# bmsSlave_main.net
KiCad netlist of a schematic drawn in Altium Designer
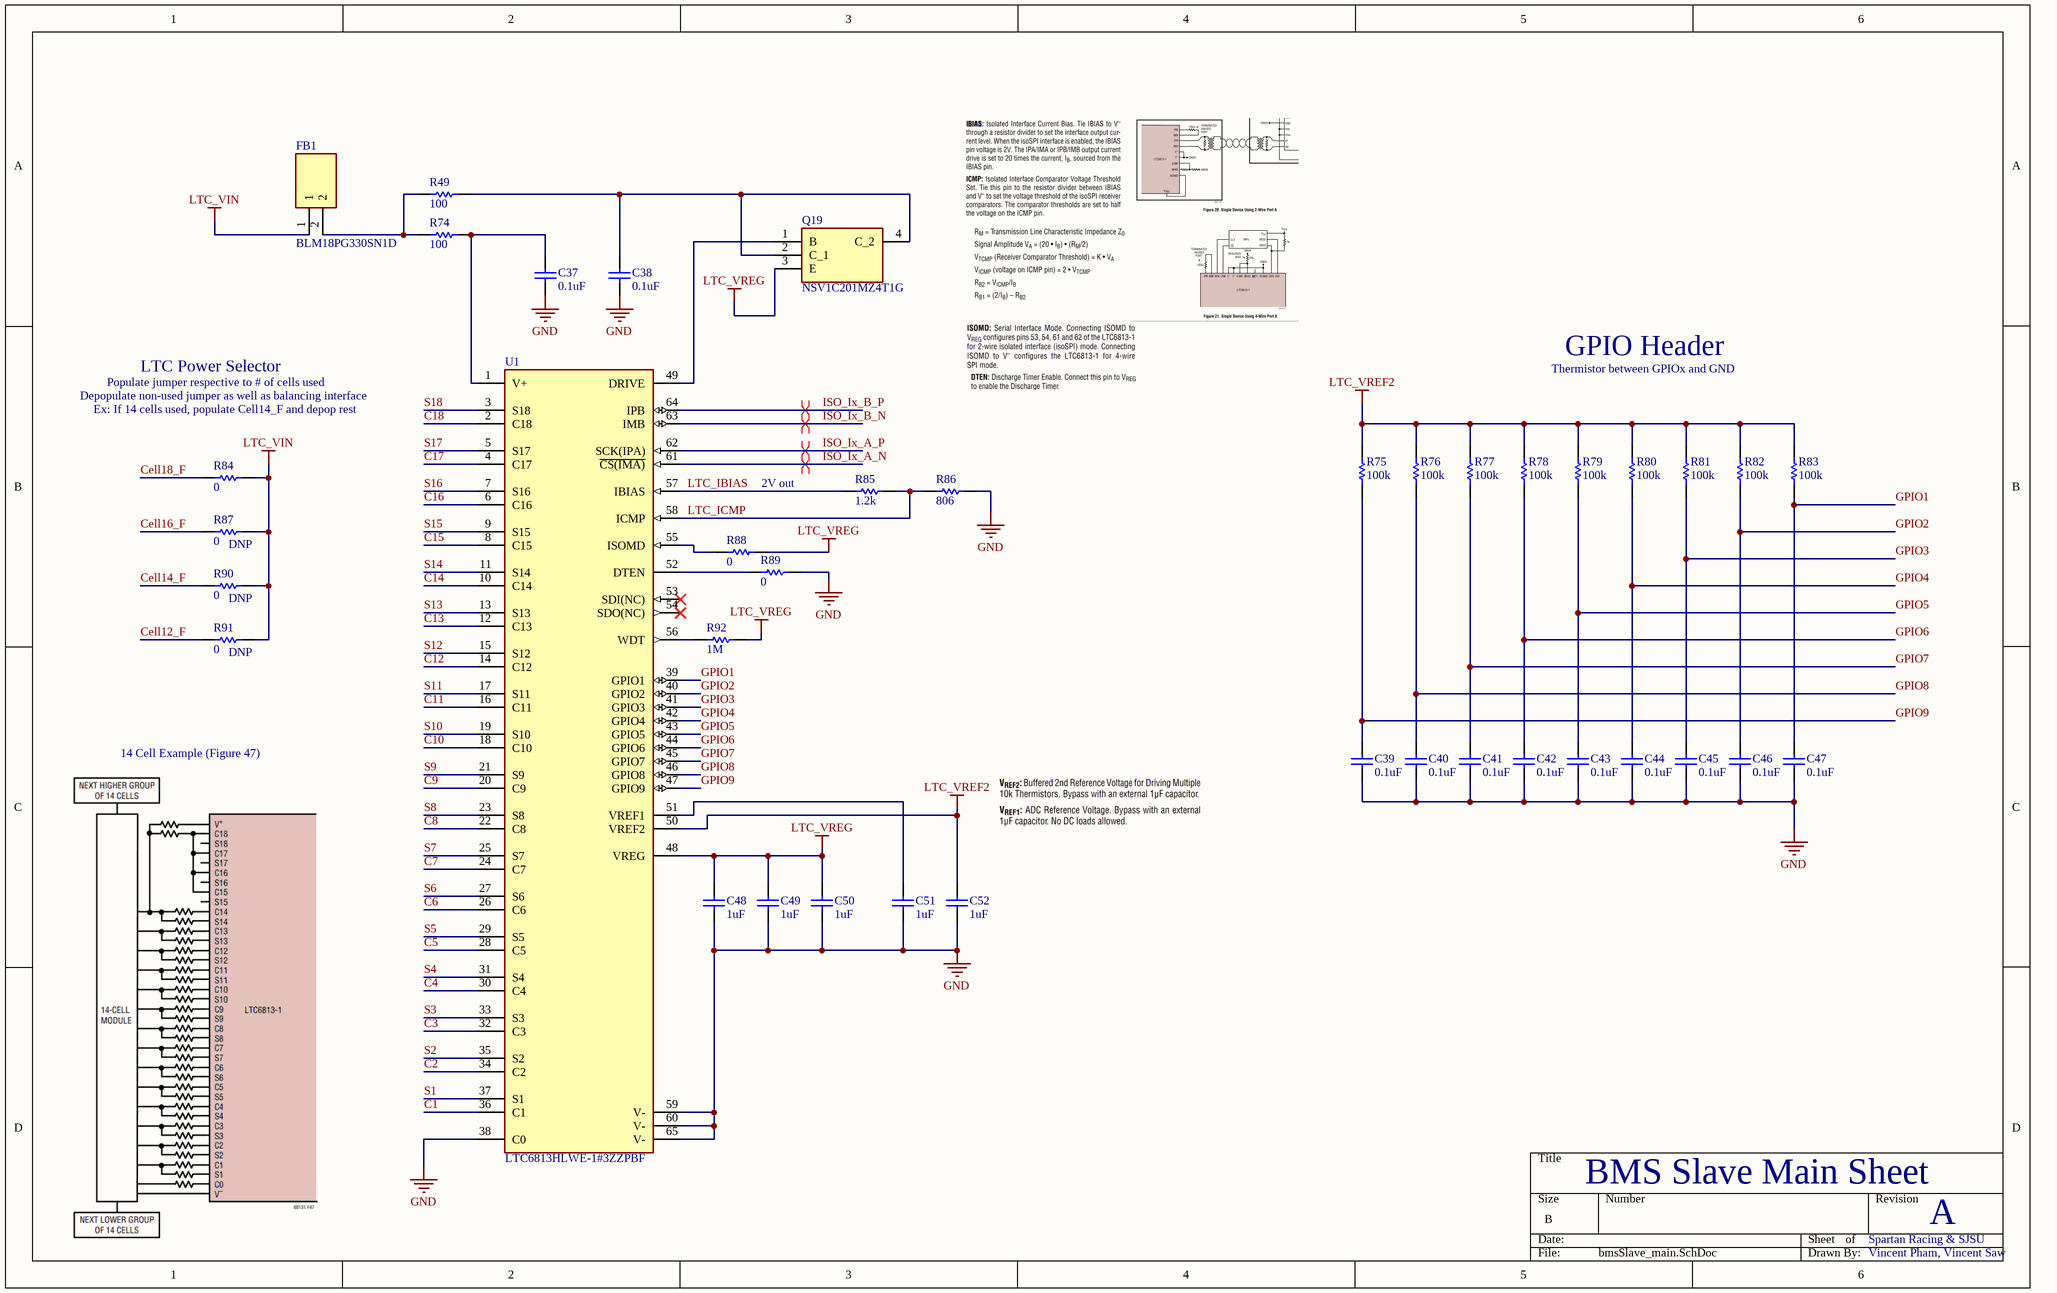
[diagram p0: bmsSlave_main.SchDoc]

(export (version "E")
  (design (tool "Eeschema 10.0.6"))
  (components
    (comp (ref "C37")
      (value "0.1uF")
      (footprint "C0603")
      (description "Capacitor")
      (libsource (lib "Simulation Generic Components") (part "Capacitor"))
    )
    (comp (ref "C38")
      (value "0.1uF")
      (footprint "C0603")
      (description "Capacitor")
      (libsource (lib "Simulation Generic Components") (part "Capacitor"))
    )
    (comp (ref "C39")
      (value "0.1uF")
      (footprint "C0603")
      (description "Capacitor")
      (libsource (lib "Simulation Generic Components") (part "Capacitor"))
    )
    (comp (ref "C40")
      (value "0.1uF")
      (footprint "C0603")
      (description "Capacitor")
      (libsource (lib "Simulation Generic Components") (part "Capacitor"))
    )
    (comp (ref "C41")
      (value "0.1uF")
      (footprint "C0603")
      (description "Capacitor")
      (libsource (lib "Simulation Generic Components") (part "Capacitor"))
    )
    (comp (ref "C42")
      (value "0.1uF")
      (footprint "C0603")
      (description "Capacitor")
      (libsource (lib "Simulation Generic Components") (part "Capacitor"))
    )
    (comp (ref "C43")
      (value "0.1uF")
      (footprint "C0603")
      (description "Capacitor")
      (libsource (lib "Simulation Generic Components") (part "Capacitor"))
    )
    (comp (ref "C44")
      (value "0.1uF")
      (footprint "C0603")
      (description "Capacitor")
      (libsource (lib "Simulation Generic Components") (part "Capacitor"))
    )
    (comp (ref "C45")
      (value "0.1uF")
      (footprint "C0603")
      (description "Capacitor")
      (libsource (lib "Simulation Generic Components") (part "Capacitor"))
    )
    (comp (ref "C46")
      (value "0.1uF")
      (footprint "C0603")
      (description "Capacitor")
      (libsource (lib "Simulation Generic Components") (part "Capacitor"))
    )
    (comp (ref "C47")
      (value "0.1uF")
      (footprint "C0603")
      (description "Capacitor")
      (libsource (lib "Simulation Generic Components") (part "Capacitor"))
    )
    (comp (ref "C48")
      (value "1uF")
      (footprint "C0603")
      (description "Capacitor")
      (libsource (lib "Simulation Generic Components") (part "Capacitor"))
    )
    (comp (ref "C49")
      (value "1uF")
      (footprint "C0603")
      (description "Capacitor")
      (libsource (lib "Simulation Generic Components") (part "Capacitor"))
    )
    (comp (ref "C50")
      (value "1uF")
      (footprint "C0603")
      (description "Capacitor")
      (libsource (lib "Simulation Generic Components") (part "Capacitor"))
    )
    (comp (ref "C51")
      (value "1uF")
      (footprint "C0603")
      (description "Capacitor")
      (libsource (lib "Simulation Generic Components") (part "Capacitor"))
    )
    (comp (ref "C52")
      (value "1uF")
      (footprint "C0603")
      (description "Capacitor")
      (libsource (lib "Simulation Generic Components") (part "Capacitor"))
    )
    (comp (ref "FB1")
      (value "BLM18PG330SN1D")
      (footprint "BEADC1608X95N")
      (description "Ferrite Bead")
      (fields (field (name "MOUSER PART NUMBER") "81-BLM18PG330SN1D"))
      (libsource (lib "bmsSlave") (part "BLM18PG330SN1D"))
    )
    (comp (ref "Q19")
      (value "NSV1C201MZ4T1G")
      (footprint "SOT230P700X175-4N:SOT230P700X175-4N")
      (description "Transistor")
      (fields (field (name "MOUSER PART NUMBER") "863-NSV1C201MZ4T1G"))
      (libsource (lib "*") (part "NSV1C201MZ4T1G"))
    )
    (comp (ref "R49")
      (value "100")
      (footprint "R0603")
      (description "Resistor")
      (libsource (lib "Simulation Generic Components") (part "Resistor"))
    )
    (comp (ref "R74")
      (value "100")
      (footprint "R0603")
      (description "Resistor")
      (libsource (lib "Simulation Generic Components") (part "Resistor"))
    )
    (comp (ref "R75")
      (value "100k")
      (footprint "R0603")
      (description "Resistor")
      (libsource (lib "Simulation Generic Components") (part "Resistor"))
    )
    (comp (ref "R76")
      (value "100k")
      (footprint "R0603")
      (description "Resistor")
      (libsource (lib "Simulation Generic Components") (part "Resistor"))
    )
    (comp (ref "R77")
      (value "100k")
      (footprint "R0603")
      (description "Resistor")
      (libsource (lib "Simulation Generic Components") (part "Resistor"))
    )
    (comp (ref "R78")
      (value "100k")
      (footprint "R0603")
      (description "Resistor")
      (libsource (lib "Simulation Generic Components") (part "Resistor"))
    )
    (comp (ref "R79")
      (value "100k")
      (footprint "R0603")
      (description "Resistor")
      (libsource (lib "Simulation Generic Components") (part "Resistor"))
    )
    (comp (ref "R80")
      (value "100k")
      (footprint "R0603")
      (description "Resistor")
      (libsource (lib "Simulation Generic Components") (part "Resistor"))
    )
    (comp (ref "R81")
      (value "100k")
      (footprint "R0603")
      (description "Resistor")
      (libsource (lib "Simulation Generic Components") (part "Resistor"))
    )
    (comp (ref "R82")
      (value "100k")
      (footprint "R0603")
      (description "Resistor")
      (libsource (lib "Simulation Generic Components") (part "Resistor"))
    )
    (comp (ref "R83")
      (value "100k")
      (footprint "R0603")
      (description "Resistor")
      (libsource (lib "Simulation Generic Components") (part "Resistor"))
    )
    (comp (ref "R84")
      (value "0")
      (footprint "R0603")
      (description "Resistor")
      (libsource (lib "Simulation Generic Components") (part "Resistor"))
    )
    (comp (ref "R85")
      (value "1.2k")
      (footprint "R0603")
      (description "Resistor")
      (libsource (lib "Simulation Generic Components") (part "Resistor"))
    )
    (comp (ref "R86")
      (value "806")
      (footprint "R0603")
      (description "Resistor")
      (libsource (lib "Simulation Generic Components") (part "Resistor"))
    )
    (comp (ref "R87")
      (value "0")
      (footprint "R0603")
      (description "Resistor")
      (libsource (lib "Simulation Generic Components") (part "Resistor"))
    )
    (comp (ref "R88")
      (value "0")
      (footprint "R0603")
      (description "Resistor")
      (libsource (lib "Simulation Generic Components") (part "Resistor"))
    )
    (comp (ref "R89")
      (value "0")
      (footprint "R0603")
      (description "Resistor")
      (libsource (lib "Simulation Generic Components") (part "Resistor"))
    )
    (comp (ref "R90")
      (value "0")
      (footprint "R0603")
      (description "Resistor")
      (libsource (lib "Simulation Generic Components") (part "Resistor"))
    )
    (comp (ref "R91")
      (value "0")
      (footprint "R0603")
      (description "Resistor")
      (libsource (lib "Simulation Generic Components") (part "Resistor"))
    )
    (comp (ref "R92")
      (value "1M")
      (footprint "R0603")
      (description "Resistor")
      (libsource (lib "Simulation Generic Components") (part "Resistor"))
    )
    (comp (ref "U1")
      (value "LTC6813HLWE-1#3ZZPBF")
      (footprint "FP-LWE-64-05-08-1982-MFG")
      (description "18 CHANNEL MULTICELL BATTERY STA")
      (fields
        (field (name "OCTOPART") "https://octopart.com/ltc6813hlwe-1%233zzpbf-analog+devices-90390400")
        (field (name "MANUFACTURER") "Analog Devices")
      )
      (libsource (lib "Altium Content Vault") (part "0b74ddd223dcb5fcd0195e222fef2b3"))
    )
  )
  (nets
    (net (code "1") (name "/C1") (class "Default")
      (node (ref "U1") (pin "36") (pinfunction "C1_36") (pintype "passive"))
    )
    (net (code "2") (name "/C2") (class "Default")
      (node (ref "U1") (pin "34") (pinfunction "C2_34") (pintype "passive"))
    )
    (net (code "3") (name "/C3") (class "Default")
      (node (ref "U1") (pin "32") (pinfunction "C3_32") (pintype "passive"))
    )
    (net (code "4") (name "/C4") (class "Default")
      (node (ref "U1") (pin "30") (pinfunction "C4_30") (pintype "passive"))
    )
    (net (code "5") (name "/C5") (class "Default")
      (node (ref "U1") (pin "28") (pinfunction "C5_28") (pintype "passive"))
    )
    (net (code "6") (name "/C6") (class "Default")
      (node (ref "U1") (pin "26") (pinfunction "C6_26") (pintype "passive"))
    )
    (net (code "7") (name "/C7") (class "Default")
      (node (ref "U1") (pin "24") (pinfunction "C7_24") (pintype "passive"))
    )
    (net (code "8") (name "/C8") (class "Default")
      (node (ref "U1") (pin "22") (pinfunction "C8_22") (pintype "passive"))
    )
    (net (code "9") (name "/C9") (class "Default")
      (node (ref "U1") (pin "20") (pinfunction "C9_20") (pintype "passive"))
    )
    (net (code "10") (name "/C10") (class "Default")
      (node (ref "U1") (pin "18") (pinfunction "C10_18") (pintype "passive"))
    )
    (net (code "11") (name "/C11") (class "Default")
      (node (ref "U1") (pin "16") (pinfunction "C11_16") (pintype "passive"))
    )
    (net (code "12") (name "/C12") (class "Default")
      (node (ref "U1") (pin "14") (pinfunction "C12_14") (pintype "passive"))
    )
    (net (code "13") (name "/C13") (class "Default")
      (node (ref "U1") (pin "12") (pinfunction "C13_12") (pintype "passive"))
    )
    (net (code "14") (name "/C14") (class "Default")
      (node (ref "U1") (pin "10") (pinfunction "C14_10") (pintype "passive"))
    )
    (net (code "15") (name "/C15") (class "Default")
      (node (ref "U1") (pin "8") (pinfunction "C15_8") (pintype "passive"))
    )
    (net (code "16") (name "/C16") (class "Default")
      (node (ref "U1") (pin "6") (pinfunction "C16_6") (pintype "passive"))
    )
    (net (code "17") (name "/C17") (class "Default")
      (node (ref "U1") (pin "4") (pinfunction "C17_4") (pintype "passive"))
    )
    (net (code "18") (name "/C18") (class "Default")
      (node (ref "U1") (pin "2") (pinfunction "C18_2") (pintype "passive"))
    )
    (net (code "19") (name "/Cell12_F") (class "Default")
      (node (ref "R91") (pin "1") (pinfunction "1_1") (pintype "passive"))
    )
    (net (code "20") (name "/Cell14_F") (class "Default")
      (node (ref "R90") (pin "1") (pinfunction "1_1") (pintype "passive"))
    )
    (net (code "21") (name "/Cell16_F") (class "Default")
      (node (ref "R87") (pin "1") (pinfunction "1_1") (pintype "passive"))
    )
    (net (code "22") (name "/Cell18_F") (class "Default")
      (node (ref "R84") (pin "1") (pinfunction "1_1") (pintype "passive"))
    )
    (net (code "23") (name "/GPIO1") (class "Default")
      (node (ref "C47") (pin "1") (pinfunction "1_1") (pintype "passive"))
      (node (ref "R83") (pin "1") (pinfunction "1_1") (pintype "passive"))
      (node (ref "U1") (pin "39") (pinfunction "GPIO1_39") (pintype "bidirectional"))
    )
    (net (code "24") (name "/GPIO2") (class "Default")
      (node (ref "C46") (pin "1") (pinfunction "1_1") (pintype "passive"))
      (node (ref "R82") (pin "1") (pinfunction "1_1") (pintype "passive"))
      (node (ref "U1") (pin "40") (pinfunction "GPIO2_40") (pintype "bidirectional"))
    )
    (net (code "25") (name "/GPIO3") (class "Default")
      (node (ref "C45") (pin "1") (pinfunction "1_1") (pintype "passive"))
      (node (ref "R81") (pin "1") (pinfunction "1_1") (pintype "passive"))
      (node (ref "U1") (pin "41") (pinfunction "GPIO3_41") (pintype "bidirectional"))
    )
    (net (code "26") (name "/GPIO4") (class "Default")
      (node (ref "C44") (pin "1") (pinfunction "1_1") (pintype "passive"))
      (node (ref "R80") (pin "1") (pinfunction "1_1") (pintype "passive"))
      (node (ref "U1") (pin "42") (pinfunction "GPIO4_42") (pintype "bidirectional"))
    )
    (net (code "27") (name "/GPIO5") (class "Default")
      (node (ref "C43") (pin "1") (pinfunction "1_1") (pintype "passive"))
      (node (ref "R79") (pin "1") (pinfunction "1_1") (pintype "passive"))
      (node (ref "U1") (pin "43") (pinfunction "GPIO5_43") (pintype "bidirectional"))
    )
    (net (code "28") (name "/GPIO6") (class "Default")
      (node (ref "C42") (pin "1") (pinfunction "1_1") (pintype "passive"))
      (node (ref "R78") (pin "1") (pinfunction "1_1") (pintype "passive"))
      (node (ref "U1") (pin "44") (pinfunction "GPIO6_44") (pintype "bidirectional"))
    )
    (net (code "29") (name "/GPIO7") (class "Default")
      (node (ref "C41") (pin "1") (pinfunction "1_1") (pintype "passive"))
      (node (ref "R77") (pin "1") (pinfunction "1_1") (pintype "passive"))
      (node (ref "U1") (pin "45") (pinfunction "GPIO7_45") (pintype "bidirectional"))
    )
    (net (code "30") (name "/GPIO8") (class "Default")
      (node (ref "C40") (pin "1") (pinfunction "1_1") (pintype "passive"))
      (node (ref "R76") (pin "1") (pinfunction "1_1") (pintype "passive"))
      (node (ref "U1") (pin "46") (pinfunction "GPIO8_46") (pintype "bidirectional"))
    )
    (net (code "31") (name "/GPIO9") (class "Default")
      (node (ref "C39") (pin "1") (pinfunction "1_1") (pintype "passive"))
      (node (ref "R75") (pin "1") (pinfunction "1_1") (pintype "passive"))
      (node (ref "U1") (pin "47") (pinfunction "GPIO9_47") (pintype "bidirectional"))
    )
    (net (code "32") (name "/ISO_Ix_A_N") (class "Default")
      (node (ref "U1") (pin "61") (pinfunction "~{CS(IMA)}_61") (pintype "input"))
    )
    (net (code "33") (name "/ISO_Ix_A_P") (class "Default")
      (node (ref "U1") (pin "62") (pinfunction "SCK(IPA)_62") (pintype "input"))
    )
    (net (code "34") (name "/ISO_Ix_B_N") (class "Default")
      (node (ref "U1") (pin "63") (pinfunction "IMB_63") (pintype "bidirectional"))
    )
    (net (code "35") (name "/ISO_Ix_B_P") (class "Default")
      (node (ref "U1") (pin "64") (pinfunction "IPB_64") (pintype "bidirectional"))
    )
    (net (code "36") (name "/LTC_IBIAS") (class "Default")
      (node (ref "R85") (pin "2") (pinfunction "2_2") (pintype "passive"))
      (node (ref "U1") (pin "57") (pinfunction "IBIAS_57") (pintype "input"))
    )
    (net (code "37") (name "/LTC_ICMP") (class "Default")
      (node (ref "R85") (pin "1") (pinfunction "1_1") (pintype "passive"))
      (node (ref "R86") (pin "1") (pinfunction "1_1") (pintype "passive"))
      (node (ref "U1") (pin "58") (pinfunction "ICMP_58") (pintype "input"))
    )
    (net (code "38") (name "/S1") (class "Default")
      (node (ref "U1") (pin "37") (pinfunction "S1_37") (pintype "passive"))
    )
    (net (code "39") (name "/S2") (class "Default")
      (node (ref "U1") (pin "35") (pinfunction "S2_35") (pintype "passive"))
    )
    (net (code "40") (name "/S3") (class "Default")
      (node (ref "U1") (pin "33") (pinfunction "S3_33") (pintype "passive"))
    )
    (net (code "41") (name "/S4") (class "Default")
      (node (ref "U1") (pin "31") (pinfunction "S4_31") (pintype "passive"))
    )
    (net (code "42") (name "/S5") (class "Default")
      (node (ref "U1") (pin "29") (pinfunction "S5_29") (pintype "passive"))
    )
    (net (code "43") (name "/S6") (class "Default")
      (node (ref "U1") (pin "27") (pinfunction "S6_27") (pintype "passive"))
    )
    (net (code "44") (name "/S7") (class "Default")
      (node (ref "U1") (pin "25") (pinfunction "S7_25") (pintype "passive"))
    )
    (net (code "45") (name "/S8") (class "Default")
      (node (ref "U1") (pin "23") (pinfunction "S8_23") (pintype "passive"))
    )
    (net (code "46") (name "/S9") (class "Default")
      (node (ref "U1") (pin "21") (pinfunction "S9_21") (pintype "passive"))
    )
    (net (code "47") (name "/S10") (class "Default")
      (node (ref "U1") (pin "19") (pinfunction "S10_19") (pintype "passive"))
    )
    (net (code "48") (name "/S11") (class "Default")
      (node (ref "U1") (pin "17") (pinfunction "S11_17") (pintype "passive"))
    )
    (net (code "49") (name "/S12") (class "Default")
      (node (ref "U1") (pin "15") (pinfunction "S12_15") (pintype "passive"))
    )
    (net (code "50") (name "/S13") (class "Default")
      (node (ref "U1") (pin "13") (pinfunction "S13_13") (pintype "passive"))
    )
    (net (code "51") (name "/S14") (class "Default")
      (node (ref "U1") (pin "11") (pinfunction "S14_11") (pintype "passive"))
    )
    (net (code "52") (name "/S15") (class "Default")
      (node (ref "U1") (pin "9") (pinfunction "S15_9") (pintype "passive"))
    )
    (net (code "53") (name "/S16") (class "Default")
      (node (ref "U1") (pin "7") (pinfunction "S16_7") (pintype "passive"))
    )
    (net (code "54") (name "/S17") (class "Default")
      (node (ref "U1") (pin "5") (pinfunction "S17_5") (pintype "passive"))
    )
    (net (code "55") (name "/S18") (class "Default")
      (node (ref "U1") (pin "3") (pinfunction "S18_3") (pintype "passive"))
    )
    (net (code "56") (name "GND") (class "Default")
      (node (ref "C37") (pin "2") (pinfunction "2_2") (pintype "passive"))
      (node (ref "C38") (pin "2") (pinfunction "2_2") (pintype "passive"))
      (node (ref "C39") (pin "2") (pinfunction "2_2") (pintype "passive"))
      (node (ref "C40") (pin "2") (pinfunction "2_2") (pintype "passive"))
      (node (ref "C41") (pin "2") (pinfunction "2_2") (pintype "passive"))
      (node (ref "C42") (pin "2") (pinfunction "2_2") (pintype "passive"))
      (node (ref "C43") (pin "2") (pinfunction "2_2") (pintype "passive"))
      (node (ref "C44") (pin "2") (pinfunction "2_2") (pintype "passive"))
      (node (ref "C45") (pin "2") (pinfunction "2_2") (pintype "passive"))
      (node (ref "C46") (pin "2") (pinfunction "2_2") (pintype "passive"))
      (node (ref "C47") (pin "2") (pinfunction "2_2") (pintype "passive"))
      (node (ref "C48") (pin "2") (pinfunction "2_2") (pintype "passive"))
      (node (ref "C49") (pin "2") (pinfunction "2_2") (pintype "passive"))
      (node (ref "C50") (pin "2") (pinfunction "2_2") (pintype "passive"))
      (node (ref "C51") (pin "2") (pinfunction "2_2") (pintype "passive"))
      (node (ref "C52") (pin "2") (pinfunction "2_2") (pintype "passive"))
      (node (ref "R86") (pin "2") (pinfunction "2_2") (pintype "passive"))
      (node (ref "R89") (pin "1") (pinfunction "1_1") (pintype "passive"))
      (node (ref "U1") (pin "38") (pinfunction "C0_38") (pintype "passive"))
      (node (ref "U1") (pin "59") (pinfunction "V-_59") (pintype "power_in"))
      (node (ref "U1") (pin "60") (pinfunction "V-_60") (pintype "power_in"))
      (node (ref "U1") (pin "65") (pinfunction "V-_65") (pintype "power_in"))
    )
    (net (code "57") (name "LTC_VIN") (class "Default")
      (node (ref "FB1") (pin "1") (pinfunction "1_1") (pintype "passive"))
      (node (ref "R84") (pin "2") (pinfunction "2_2") (pintype "passive"))
      (node (ref "R87") (pin "2") (pinfunction "2_2") (pintype "passive"))
      (node (ref "R90") (pin "2") (pinfunction "2_2") (pintype "passive"))
      (node (ref "R91") (pin "2") (pinfunction "2_2") (pintype "passive"))
    )
    (net (code "58") (name "LTC_VREF2") (class "Default")
      (node (ref "C52") (pin "1") (pinfunction "1_1") (pintype "passive"))
      (node (ref "R75") (pin "2") (pinfunction "2_2") (pintype "passive"))
      (node (ref "R76") (pin "2") (pinfunction "2_2") (pintype "passive"))
      (node (ref "R77") (pin "2") (pinfunction "2_2") (pintype "passive"))
      (node (ref "R78") (pin "2") (pinfunction "2_2") (pintype "passive"))
      (node (ref "R79") (pin "2") (pinfunction "2_2") (pintype "passive"))
      (node (ref "R80") (pin "2") (pinfunction "2_2") (pintype "passive"))
      (node (ref "R81") (pin "2") (pinfunction "2_2") (pintype "passive"))
      (node (ref "R82") (pin "2") (pinfunction "2_2") (pintype "passive"))
      (node (ref "R83") (pin "2") (pinfunction "2_2") (pintype "passive"))
      (node (ref "U1") (pin "50") (pinfunction "VREF2_50") (pintype "power_in"))
    )
    (net (code "59") (name "LTC_VREG") (class "Default")
      (node (ref "C48") (pin "1") (pinfunction "1_1") (pintype "passive"))
      (node (ref "C49") (pin "1") (pinfunction "1_1") (pintype "passive"))
      (node (ref "C50") (pin "1") (pinfunction "1_1") (pintype "passive"))
      (node (ref "Q19") (pin "3") (pinfunction "E_3") (pintype "passive"))
      (node (ref "R88") (pin "1") (pinfunction "1_1") (pintype "passive"))
      (node (ref "R92") (pin "1") (pinfunction "1_1") (pintype "passive"))
      (node (ref "U1") (pin "48") (pinfunction "VREG_48") (pintype "power_in"))
    )
    (net (code "60") (name "Net-(FB1-Pad2)") (class "Default")
      (node (ref "FB1") (pin "2") (pinfunction "2_2") (pintype "passive"))
      (node (ref "R49") (pin "1") (pinfunction "1_1") (pintype "passive"))
      (node (ref "R74") (pin "1") (pinfunction "1_1") (pintype "passive"))
    )
    (net (code "61") (name "Net-(Q19-B)") (class "Default")
      (node (ref "Q19") (pin "1") (pinfunction "B_1") (pintype "passive"))
      (node (ref "U1") (pin "49") (pinfunction "DRIVE_49") (pintype "power_in"))
    )
    (net (code "62") (name "Net-(Q19-C_1)") (class "Default")
      (node (ref "C38") (pin "1") (pinfunction "1_1") (pintype "passive"))
      (node (ref "Q19") (pin "2") (pinfunction "C_1_2") (pintype "passive"))
      (node (ref "Q19") (pin "4") (pinfunction "C_2_4") (pintype "passive"))
      (node (ref "R49") (pin "2") (pinfunction "2_2") (pintype "passive"))
    )
    (net (code "63") (name "Net-(U1-DTEN)") (class "Default")
      (node (ref "R89") (pin "2") (pinfunction "2_2") (pintype "passive"))
      (node (ref "U1") (pin "52") (pinfunction "DTEN_52") (pintype "power_in"))
    )
    (net (code "64") (name "Net-(U1-ISOMD)") (class "Default")
      (node (ref "R88") (pin "2") (pinfunction "2_2") (pintype "passive"))
      (node (ref "U1") (pin "55") (pinfunction "ISOMD_55") (pintype "input"))
    )
    (net (code "65") (name "Net-(U1-V+)") (class "Default")
      (node (ref "C37") (pin "1") (pinfunction "1_1") (pintype "passive"))
      (node (ref "R74") (pin "2") (pinfunction "2_2") (pintype "passive"))
      (node (ref "U1") (pin "1") (pinfunction "V+_1") (pintype "power_in"))
    )
    (net (code "66") (name "Net-(U1-VREF1)") (class "Default")
      (node (ref "C51") (pin "1") (pinfunction "1_1") (pintype "passive"))
      (node (ref "U1") (pin "51") (pinfunction "VREF1_51") (pintype "power_in"))
    )
    (net (code "67") (name "Net-(U1-WDT)") (class "Default")
      (node (ref "R92") (pin "2") (pinfunction "2_2") (pintype "passive"))
      (node (ref "U1") (pin "56") (pinfunction "WDT_56") (pintype "output"))
    )
    (net (code "68") (name "unconnected-(U1-SDI(NC)-Pad53)") (class "Default")
      (node (ref "U1") (pin "53") (pinfunction "SDI(NC)_53") (pintype "input+no_connect"))
    )
    (net (code "69") (name "unconnected-(U1-SDO(NC)-Pad54)") (class "Default")
      (node (ref "U1") (pin "54") (pinfunction "SDO(NC)_54") (pintype "output+no_connect"))
    )
  )
)
